# MotorDriver.net
KiCad netlist of a schematic drawn in Altium Designer
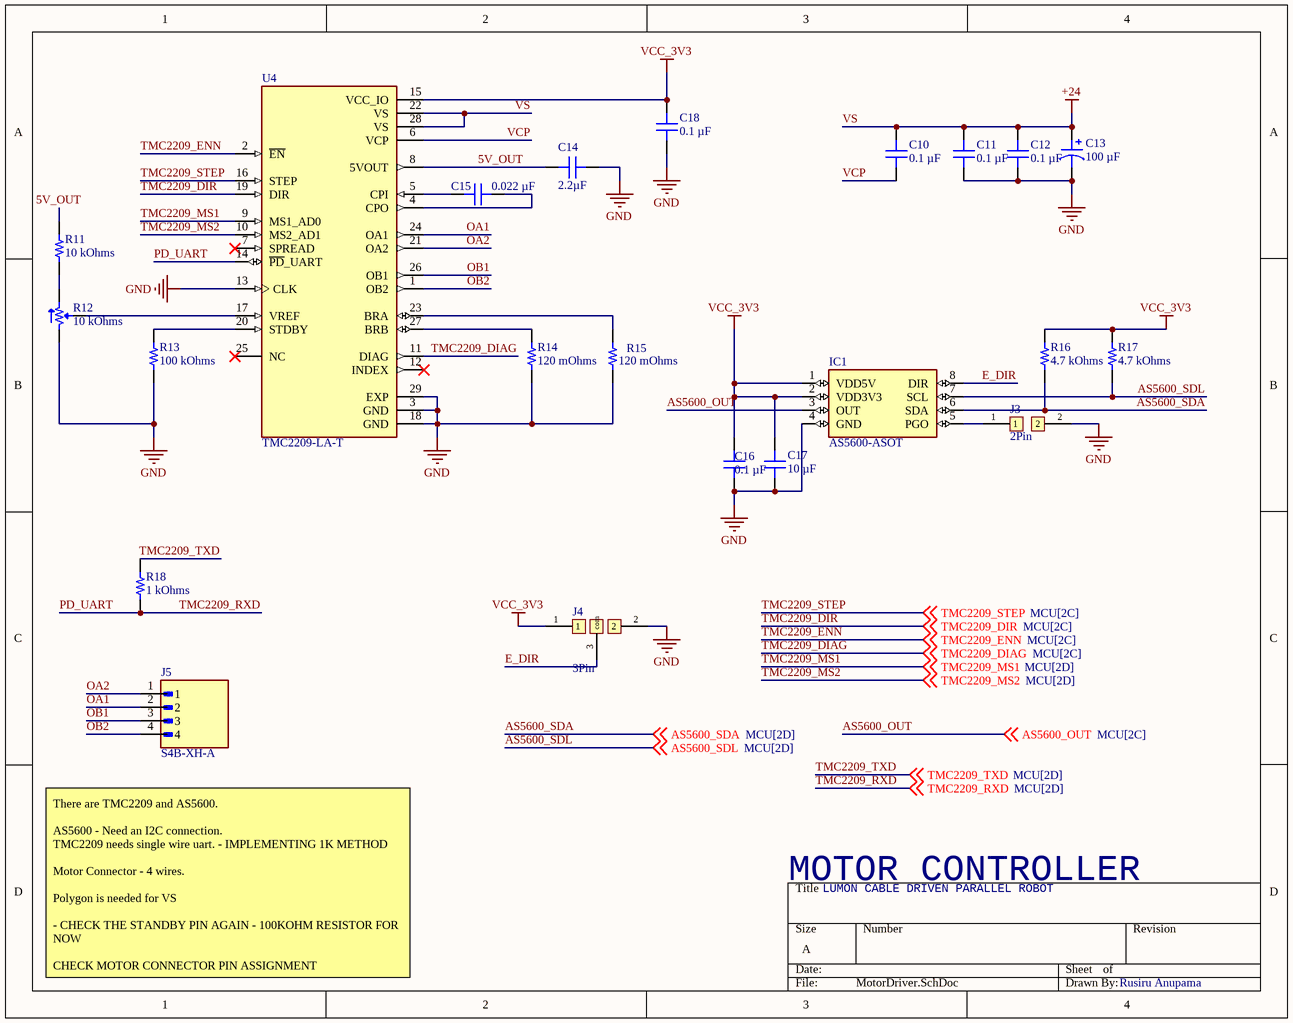
[diagram p0: MotorDriver.SchDoc]

(export (version "E")
  (design (tool "Eeschema 10.0.6"))
  (components
    (comp (ref "C10")
      (value "0.1 µF")
      (footprint "CAP 0805_2012")
      (description "CAP CER 0.1UF 50V X7R 0805")
      (fields
        (field (name "PART NUMBER") "CC0805MRX7R9BB104")
        (field (name "CAPACITANCE") "0.1 µF")
        (field (name "MANUFACTURER") "Yageo")
      )
      (libsource (lib "Celestial Altium Library - altium_library") (part "Capacitor"))
    )
    (comp (ref "C11")
      (value "0.1 µF")
      (footprint "CAP 0805_2012")
      (description "CAP CER 0.1UF 50V X7R 0805")
      (fields
        (field (name "PART NUMBER") "CC0805MRX7R9BB104")
        (field (name "CAPACITANCE") "0.1 µF")
        (field (name "MANUFACTURER") "Yageo")
      )
      (libsource (lib "Celestial Altium Library - altium_library") (part "Capacitor"))
    )
    (comp (ref "C12")
      (value "0.1 µF")
      (footprint "CAP 0805_2012")
      (description "CAP CER 0.1UF 50V X7R 0805")
      (fields
        (field (name "PART NUMBER") "CC0805MRX7R9BB104")
        (field (name "CAPACITANCE") "0.1 µF")
        (field (name "MANUFACTURER") "Yageo")
      )
      (libsource (lib "Celestial Altium Library - altium_library") (part "Capacitor"))
    )
    (comp (ref "C13")
      (value "100 µF")
      (footprint "CAP ALSMD 8.3MM H10.5MM")
      (description "CAP ALUM 100UF 20% 50V SMD")
      (fields (field (name "PART NUMBER") "50SKV100M8X10.5") (field (name "MANUFACTURER") "Rubycon"))
      (libsource (lib "Celestial Altium Library - altium_library") (part "Polarised Capacitor"))
    )
    (comp (ref "C14")
      (value "2.2µF")
      (footprint "CAP 0805_2012")
      (description "CAP CER 2.2UF 16V X5R 0805")
      (fields
        (field (name "PART NUMBER") "0805YD225KAT2A")
        (field (name "CAPACITANCE") "2.2µF")
        (field (name "MANUFACTURER") "AVX Corporation")
      )
      (libsource (lib "Celestial Altium Library - altium_library") (part "Capacitor"))
    )
    (comp (ref "C15")
      (value "0.022 µF")
      (footprint "CAP 0805_2012")
      (description "CAP CER 0805 22NF 50V X7R 10%")
      (fields
        (field (name "PART NUMBER") "C0805X223K5REC7210")
        (field (name "CAPACITANCE") "0.022 µF")
        (field (name "MANUFACTURER") "KEMET")
      )
      (libsource (lib "Celestial Altium Library - altium_library") (part "Capacitor"))
    )
    (comp (ref "C16")
      (value "0.1 µF")
      (footprint "CAP 0805_2012")
      (description "CAP CER 0.1UF 50V X7R 0805")
      (fields
        (field (name "PART NUMBER") "CC0805MRX7R9BB104")
        (field (name "CAPACITANCE") "0.1 µF")
        (field (name "MANUFACTURER") "Yageo")
      )
      (libsource (lib "Celestial Altium Library - altium_library") (part "Capacitor"))
    )
    (comp (ref "C17")
      (value "10 µF")
      (footprint "CAP 0805_2012")
      (description "CAP CER 10UF 10V X7S 0805")
      (fields
        (field (name "PART NUMBER") "CL21Y106KPQVPNE")
        (field (name "CAPACITANCE") "10 µF")
        (field (name "MANUFACTURER") "Samsung Electro-Mechanics")
      )
      (libsource (lib "Celestial Altium Library - altium_library") (part "Capacitor"))
    )
    (comp (ref "C18")
      (value "0.1 µF")
      (footprint "CAP 0805_2012")
      (description "CAP CER 0.1UF 50V X7R 0805")
      (fields
        (field (name "PART NUMBER") "CC0805MRX7R9BB104")
        (field (name "CAPACITANCE") "0.1 µF")
        (field (name "MANUFACTURER") "Yageo")
      )
      (libsource (lib "Celestial Altium Library - altium_library") (part "Capacitor"))
    )
    (comp (ref "IC1")
      (value "AS5600-ASOT")
      (footprint "SOIC127P600X175-8N")
      (description "Hall Effect Sensor Angle External Magnet, Not Included Gull Wing")
      (fields (field (name "MF") "ams") (field (name "LSCS PART #") "C499458"))
      (libsource (lib "Actuator Lib") (part "AS5600-ASOT"))
    )
    (comp (ref "J3") (value "2Pin") (footprint "2Pin") (libsource (lib "Actuator Lib") (part "2Pin")))
    (comp (ref "J4")
      (value "3Pin")
      (footprint "Solder_Bridge")
      (libsource (lib "Actuator Lib") (part "3Pin"))
    )
    (comp (ref "J5")
      (value "S4B-XH-A")
      (footprint "JST_S4B-XH-A")
      (fields (field (name "LCSC PART #") "C19271397"))
      (libsource (lib "Actuator Lib") (part "S4B-XH-A"))
    )
    (comp (ref "R11")
      (value "10 kOhms")
      (footprint "RES 0805_2012")
      (description "RES SMD 10K OHM 0.1% 1/10W 0805")
      (fields
        (field (name "PART NUMBER") "CPF0805B10KE")
        (field (name "MANUFACTURER") "TE Connectivity Passive Product")
      )
      (libsource (lib "Celestial Altium Library - altium_library") (part "Resistor"))
    )
    (comp (ref "R12")
      (value "10 kOhms")
      (footprint "POT BOURNS TRIMPOT TC33")
      (description "TRIMMER 10K OHM 0.15W J LEAD TOP")
      (fields (field (name "PART NUMBER") "TC33X-2-103E") (field (name "MANUFACTURER") "Bourns Inc."))
      (libsource (lib "Celestial Altium Library - altium_library") (part "Potentiometer"))
    )
    (comp (ref "R13")
      (value "100 kOhms")
      (footprint "RES 0805_2012")
      (description "RES SMD 100K OHM 1% 1/2W 0805")
      (fields (field (name "PART NUMBER") "RCS0805100KFKEA") (field (name "MANUFACTURER") "Vishay Dale"))
      (libsource (lib "Celestial Altium Library - altium_library") (part "Resistor"))
    )
    (comp (ref "R14")
      (value "120 mOhms")
      (footprint "RES 1206_3216")
      (description "RES 0.12 OHM 1% 3/4W 1206")
      (fields (field (name "PART NUMBER") "KRL1632E-M-R120-F-T5") (field (name "MANUFACTURER") "Susumu"))
      (libsource (lib "Celestial Altium Library - altium_library") (part "Resistor"))
    )
    (comp (ref "R15")
      (value "120 mOhms")
      (footprint "RES 1206_3216")
      (description "RES 0.12 OHM 1% 3/4W 1206")
      (fields (field (name "PART NUMBER") "KRL1632E-M-R120-F-T5") (field (name "MANUFACTURER") "Susumu"))
      (libsource (lib "Celestial Altium Library - altium_library") (part "Resistor"))
    )
    (comp (ref "R16")
      (value "4.7 kOhms")
      (footprint "RES 0805_2012")
      (description "RES SMD 4.7K OHM 5% 1/2W 0805")
      (fields (field (name "PART NUMBER") "RCS08054K70JNEA") (field (name "MANUFACTURER") "Vishay Dale"))
      (libsource (lib "Celestial Altium Library - altium_library") (part "Resistor"))
    )
    (comp (ref "R17")
      (value "4.7 kOhms")
      (footprint "RES 0805_2012")
      (description "RES SMD 4.7K OHM 5% 1/2W 0805")
      (fields (field (name "PART NUMBER") "RCS08054K70JNEA") (field (name "MANUFACTURER") "Vishay Dale"))
      (libsource (lib "Celestial Altium Library - altium_library") (part "Resistor"))
    )
    (comp (ref "R18")
      (value "1 kOhms")
      (footprint "RES 0805_2012")
      (description "RES 1K OHM 0.1% 1/10W 0805")
      (fields
        (field (name "PART NUMBER") "RNCS0805BKE1K00")
        (field (name "MANUFACTURER") "Stackpole Electronics Inc")
      )
      (libsource (lib "Celestial Altium Library - altium_library") (part "Resistor"))
    )
    (comp (ref "U4")
      (value "TMC2209-LA-T")
      (footprint "QFN50P500X500X90-29N")
      (description "Bipolar Motor Driver Power MOSFET Step/Direction, UART 28-QFN (5x5)")
      (fields (field (name "MF") "Trinamic Motion Control GmbH") (field (name "LCSC PART #") "C2150710"))
      (libsource (lib "Actuator Lib") (part "TMC2209-LA-T"))
    )
  )
  (nets
    (net (code "1") (name "+24") (class "Default")
      (node (ref "C10") (pin "1") (pinfunction "1_1") (pintype "passive"))
      (node (ref "C11") (pin "2") (pinfunction "2_2") (pintype "passive"))
      (node (ref "C12") (pin "2") (pinfunction "2_2") (pintype "passive"))
      (node (ref "C13") (pin "1") (pinfunction "1_1") (pintype "passive"))
      (node (ref "U4") (pin "22") (pinfunction "VS_22") (pintype "power_in"))
      (node (ref "U4") (pin "28") (pinfunction "VS_28") (pintype "power_in"))
    )
    (net (code "2") (name "/5V_OUT") (class "Default")
      (node (ref "C14") (pin "1") (pinfunction "1_1") (pintype "passive"))
      (node (ref "R11") (pin "2") (pinfunction "2_2") (pintype "passive"))
      (node (ref "U4") (pin "8") (pinfunction "5VOUT_8") (pintype "output"))
    )
    (net (code "3") (name "/E_DIR") (class "Default")
      (node (ref "IC1") (pin "8") (pinfunction "DIR_8") (pintype "bidirectional"))
      (node (ref "J4") (pin "3") (pinfunction "com_3") (pintype "passive"))
    )
    (net (code "4") (name "/OA1") (class "Default")
      (node (ref "J5") (pin "2") (pinfunction "2_2") (pintype "passive"))
      (node (ref "U4") (pin "24") (pinfunction "OA1_24") (pintype "output"))
    )
    (net (code "5") (name "/OA2") (class "Default")
      (node (ref "J5") (pin "1") (pinfunction "1_1") (pintype "passive"))
      (node (ref "U4") (pin "21") (pinfunction "OA2_21") (pintype "output"))
    )
    (net (code "6") (name "/OB1") (class "Default")
      (node (ref "J5") (pin "3") (pinfunction "3_3") (pintype "passive"))
      (node (ref "U4") (pin "26") (pinfunction "OB1_26") (pintype "output"))
    )
    (net (code "7") (name "/OB2") (class "Default")
      (node (ref "J5") (pin "4") (pinfunction "4_4") (pintype "passive"))
      (node (ref "U4") (pin "1") (pinfunction "OB2_1") (pintype "output"))
    )
    (net (code "8") (name "/VCP") (class "Default")
      (node (ref "C10") (pin "2") (pinfunction "2_2") (pintype "passive"))
      (node (ref "U4") (pin "6") (pinfunction "VCP_6") (pintype "power_in"))
    )
    (net (code "9") (name "AS5600_OUT") (class "Default")
      (node (ref "IC1") (pin "3") (pinfunction "OUT_3") (pintype "bidirectional"))
    )
    (net (code "10") (name "AS5600_SDA") (class "Default")
      (node (ref "IC1") (pin "6") (pinfunction "SDA_6") (pintype "bidirectional"))
      (node (ref "R16") (pin "1") (pinfunction "1_1") (pintype "passive"))
    )
    (net (code "11") (name "AS5600_SDL") (class "Default")
      (node (ref "IC1") (pin "7") (pinfunction "SCL_7") (pintype "bidirectional"))
      (node (ref "R17") (pin "1") (pinfunction "1_1") (pintype "passive"))
    )
    (net (code "12") (name "GND") (class "Default")
      (node (ref "C11") (pin "1") (pinfunction "1_1") (pintype "passive"))
      (node (ref "C12") (pin "1") (pinfunction "1_1") (pintype "passive"))
      (node (ref "C13") (pin "2") (pinfunction "2_2") (pintype "passive"))
      (node (ref "C14") (pin "2") (pinfunction "2_2") (pintype "passive"))
      (node (ref "C16") (pin "1") (pinfunction "1_1") (pintype "passive"))
      (node (ref "C17") (pin "1") (pinfunction "1_1") (pintype "passive"))
      (node (ref "C18") (pin "1") (pinfunction "1_1") (pintype "passive"))
      (node (ref "IC1") (pin "4") (pinfunction "GND_4") (pintype "bidirectional"))
      (node (ref "J3") (pin "2") (pinfunction "2_2") (pintype "passive"))
      (node (ref "J4") (pin "2") (pinfunction "2_2") (pintype "passive"))
      (node (ref "R12") (pin "1") (pinfunction "1_1") (pintype "passive"))
      (node (ref "R13") (pin "1") (pinfunction "1_1") (pintype "passive"))
      (node (ref "R14") (pin "1") (pinfunction "1_1") (pintype "passive"))
      (node (ref "R15") (pin "1") (pinfunction "1_1") (pintype "passive"))
      (node (ref "U4") (pin "13") (pinfunction "CLK_13") (pintype "input"))
      (node (ref "U4") (pin "18") (pinfunction "GND_18") (pintype "power_in"))
      (node (ref "U4") (pin "29") (pinfunction "EXP_29") (pintype "power_in"))
      (node (ref "U4") (pin "3") (pinfunction "GND_3") (pintype "power_in"))
    )
    (net (code "13") (name "Net-(IC1-PGO)") (class "Default")
      (node (ref "IC1") (pin "5") (pinfunction "PGO_5") (pintype "bidirectional"))
      (node (ref "J3") (pin "1") (pinfunction "1_1") (pintype "passive"))
    )
    (net (code "14") (name "Net-(R11-Pad1)") (class "Default")
      (node (ref "R11") (pin "1") (pinfunction "1_1") (pintype "passive"))
      (node (ref "R12") (pin "3") (pinfunction "3_3") (pintype "passive"))
    )
    (net (code "15") (name "Net-(U4-BRA)") (class "Default")
      (node (ref "R15") (pin "2") (pinfunction "2_2") (pintype "passive"))
      (node (ref "U4") (pin "23") (pinfunction "BRA_23") (pintype "bidirectional"))
    )
    (net (code "16") (name "Net-(U4-BRB)") (class "Default")
      (node (ref "R14") (pin "2") (pinfunction "2_2") (pintype "passive"))
      (node (ref "U4") (pin "27") (pinfunction "BRB_27") (pintype "bidirectional"))
    )
    (net (code "17") (name "Net-(U4-CPI)") (class "Default")
      (node (ref "C15") (pin "2") (pinfunction "2_2") (pintype "passive"))
      (node (ref "U4") (pin "5") (pinfunction "CPI_5") (pintype "input"))
    )
    (net (code "18") (name "Net-(U4-CPO)") (class "Default")
      (node (ref "C15") (pin "1") (pinfunction "1_1") (pintype "passive"))
      (node (ref "U4") (pin "4") (pinfunction "CPO_4") (pintype "output"))
    )
    (net (code "19") (name "Net-(U4-STDBY)") (class "Default")
      (node (ref "R13") (pin "2") (pinfunction "2_2") (pintype "passive"))
      (node (ref "U4") (pin "20") (pinfunction "STDBY_20") (pintype "input"))
    )
    (net (code "20") (name "Net-(U4-VREF)") (class "Default")
      (node (ref "R12") (pin "2") (pinfunction "2_2") (pintype "passive"))
      (node (ref "U4") (pin "17") (pinfunction "VREF_17") (pintype "input"))
    )
    (net (code "21") (name "TMC2209_DIAG") (class "Default")
      (node (ref "U4") (pin "11") (pinfunction "DIAG_11") (pintype "output"))
    )
    (net (code "22") (name "TMC2209_DIR") (class "Default")
      (node (ref "U4") (pin "19") (pinfunction "DIR_19") (pintype "input"))
    )
    (net (code "23") (name "TMC2209_ENN") (class "Default")
      (node (ref "U4") (pin "2") (pinfunction "~{EN}_2") (pintype "input"))
    )
    (net (code "24") (name "TMC2209_MS1") (class "Default")
      (node (ref "U4") (pin "9") (pinfunction "MS1_AD0_9") (pintype "input"))
    )
    (net (code "25") (name "TMC2209_MS2") (class "Default")
      (node (ref "U4") (pin "10") (pinfunction "MS2_AD1_10") (pintype "input"))
    )
    (net (code "26") (name "TMC2209_RXD") (class "Default")
      (node (ref "R18") (pin "1") (pinfunction "1_1") (pintype "passive"))
      (node (ref "U4") (pin "14") (pinfunction "~{PD}_UART_14") (pintype "bidirectional"))
    )
    (net (code "27") (name "TMC2209_STEP") (class "Default")
      (node (ref "U4") (pin "16") (pinfunction "STEP_16") (pintype "input"))
    )
    (net (code "28") (name "TMC2209_TXD") (class "Default")
      (node (ref "R18") (pin "2") (pinfunction "2_2") (pintype "passive"))
    )
    (net (code "29") (name "VCC_3V3") (class "Default")
      (node (ref "C16") (pin "2") (pinfunction "2_2") (pintype "passive"))
      (node (ref "C17") (pin "2") (pinfunction "2_2") (pintype "passive"))
      (node (ref "C18") (pin "2") (pinfunction "2_2") (pintype "passive"))
      (node (ref "IC1") (pin "1") (pinfunction "VDD5V_1") (pintype "bidirectional"))
      (node (ref "IC1") (pin "2") (pinfunction "VDD3V3_2") (pintype "bidirectional"))
      (node (ref "J4") (pin "1") (pinfunction "1_1") (pintype "passive"))
      (node (ref "R16") (pin "2") (pinfunction "2_2") (pintype "passive"))
      (node (ref "R17") (pin "2") (pinfunction "2_2") (pintype "passive"))
      (node (ref "U4") (pin "15") (pinfunction "VCC_IO_15") (pintype "power_in"))
    )
    (net (code "30") (name "unconnected-(U4-INDEX-Pad12)") (class "Default")
      (node (ref "U4") (pin "12") (pinfunction "INDEX_12") (pintype "output+no_connect"))
    )
    (net (code "31") (name "unconnected-(U4-NC-Pad25)") (class "Default")
      (node (ref "U4") (pin "25") (pinfunction "NC_25") (pintype "passive+no_connect"))
    )
    (net (code "32") (name "unconnected-(U4-SPREAD-Pad7)") (class "Default")
      (node (ref "U4") (pin "7") (pinfunction "SPREAD_7") (pintype "input+no_connect"))
    )
  )
)
